# 06-SIM800C.net
KiCad netlist of a schematic drawn in Altium Designer
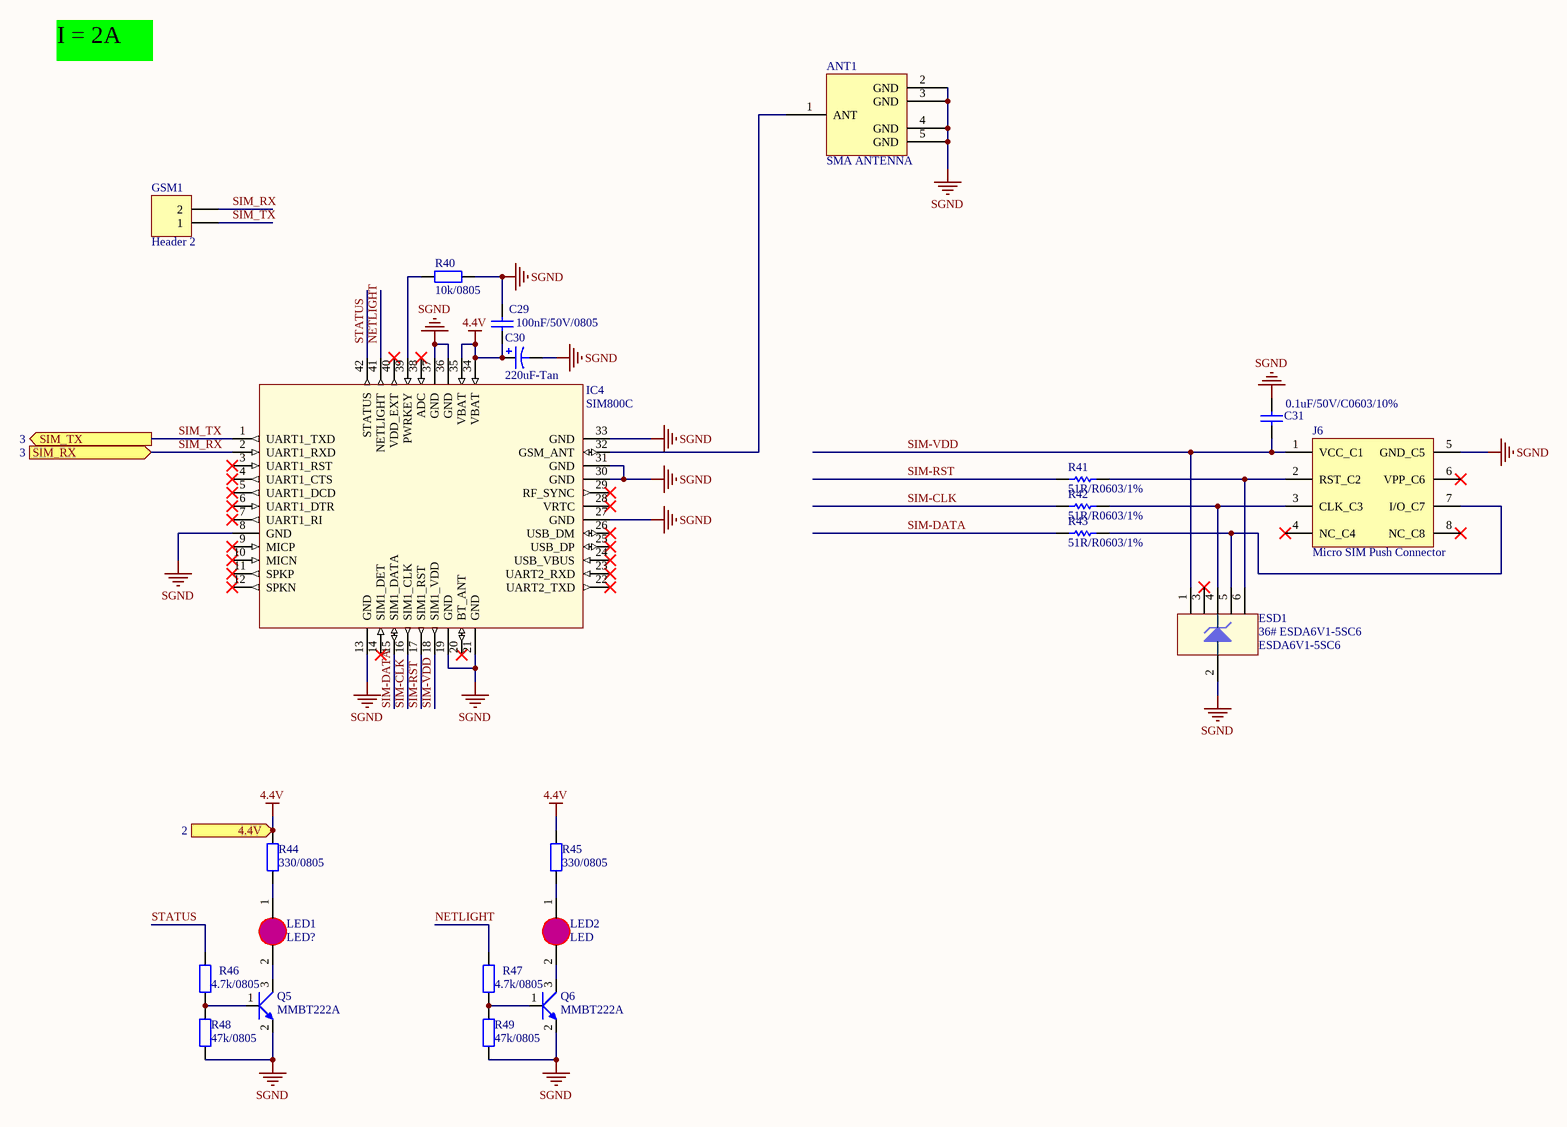
[diagram p0: 06-SIM800C.SchDoc]

(export (version "E")
  (design (tool "Eeschema 10.0.6"))
  (components
    (comp (ref "ANT1")
      (value "SMA ANTENNA")
      (footprint "ANT-SMA-ST-F")
      (libsource (lib "Air_System_lib") (part "SMA ANTENNA"))
    )
    (comp (ref "C29")
      (value "100nF/50V/0805")
      (footprint "Cap Ceramic 0805 SMD")
      (fields (field (name "PUBLISHER") "Altium Limited"))
      (libsource (lib "NBBLib 14-03-2012") (part "CapSMD"))
    )
    (comp (ref "C30")
      (value "220uF-Tan")
      (footprint "CAP TANT CASE E SMD")
      (libsource (lib "Air_System_lib") (part "CAP1210-Tan"))
    )
    (comp (ref "C31")
      (value "0.1uF/50V/C0603/10%")
      (footprint "Cap Ceramic 0603 SMD")
      (description "CAP CER 0.1UF 50V 10% X7R 0603")
      (fields
        (field (name "MANUFACTURER") "Murata Electronics North America")
        (field (name "MANUFACTURER PART NUMBER") "GRM188R71H104KA93D")
      )
      (libsource (lib "GSHT_181013") (part "0.1uF/50V/C0603/10%"))
    )
    (comp (ref "ESD1")
      (value "36# ESDA6V1-5SC6")
      (footprint "36# ESDA6V1-5SC6")
      (description "TRANSIL™ ARRAY FOR ESD PROTECTION")
      (fields (field (name "SUPPLIER PART NUMBER 1") "ESDA6V1-5SC6"))
      (libsource (lib "GSHT_181013") (part "36# ESDA6V1-5SC6"))
    )
    (comp (ref "GSM1")
      (value "Header 2")
      (footprint "Header_2")
      (description "Header, 2-Pin")
      (fields (field (name "PUBLISHER") "Altium Limited"))
      (libsource (lib "NBBLib 14-03-2012") (part "Header 2"))
    )
    (comp (ref "IC4")
      (value "SIM800C")
      (footprint "SIM800C")
      (description "SIM800C V1.00")
      (libsource (lib "LIEMTHANH_LIB") (part "SIM800C"))
    )
    (comp (ref "J6")
      (value "Micro SIM Push Connector")
      (footprint "9# SIM holder")
      (libsource (lib "GSHT_181013") (part "9#SIM Card Holder KF-016"))
    )
    (comp (ref "LED1")
      (value "LED?")
      (footprint "Led 0805R")
      (description "LED SMD 0805")
      (libsource (lib "NBBLib 14-03-2012") (part "LED0805"))
    )
    (comp (ref "LED2")
      (value "LED")
      (footprint "Led 0805R")
      (description "LED SMD 0805")
      (libsource (lib "NBBLib 14-03-2012") (part "LED0805"))
    )
    (comp (ref "Q5")
      (value "MMBT222A")
      (footprint "MMBT2222A")
      (libsource (lib "Air_System_lib") (part "MMBT222A"))
    )
    (comp (ref "Q6")
      (value "MMBT222A")
      (footprint "MMBT2222A")
      (libsource (lib "Air_System_lib") (part "MMBT222A"))
    )
    (comp (ref "R40")
      (value "10k/0805")
      (footprint "RESC2012(0805)")
      (description "Resistor SMD 0805")
      (fields (field (name "PUBLISHER") "Altium Limited"))
      (libsource (lib "") (part "R0805_1"))
    )
    (comp (ref "R41")
      (value "51R/R0603/1%")
      (footprint "Res 0603 SMD")
      (description "RES SMD 22 OHM 1% 1/10W 0603")
      (fields
        (field (name "MANUFACTURER") "Yageo")
        (field (name "MANUFACTURER PART NUMBER") "RC0603FR-0722RL")
      )
      (libsource (lib "GSHT_181013") (part "22R/R0603/1%"))
    )
    (comp (ref "R42")
      (value "51R/R0603/1%")
      (footprint "Res 0603 SMD")
      (description "RES SMD 22 OHM 1% 1/10W 0603")
      (fields
        (field (name "MANUFACTURER") "Yageo")
        (field (name "MANUFACTURER PART NUMBER") "RC0603FR-0722RL")
      )
      (libsource (lib "GSHT_181013") (part "22R/R0603/1%"))
    )
    (comp (ref "R43")
      (value "51R/R0603/1%")
      (footprint "Res 0603 SMD")
      (description "RES SMD 22 OHM 1% 1/10W 0603")
      (fields
        (field (name "MANUFACTURER") "Yageo")
        (field (name "MANUFACTURER PART NUMBER") "RC0603FR-0722RL")
      )
      (libsource (lib "GSHT_181013") (part "22R/R0603/1%"))
    )
    (comp (ref "R44")
      (value "330/0805")
      (footprint "RESC2012(0805)")
      (description "Resistor SMD 0805")
      (fields (field (name "Comment") "R0805") (field (name "PUBLISHER") "Altium Limited"))
      (libsource (lib "NBBLib 14-03-2012") (part "R0805"))
    )
    (comp (ref "R45")
      (value "330/0805")
      (footprint "RESC2012(0805)")
      (description "Resistor SMD 0805")
      (fields (field (name "Comment") "R0805") (field (name "PUBLISHER") "Altium Limited"))
      (libsource (lib "NBBLib 14-03-2012") (part "R0805"))
    )
    (comp (ref "R46")
      (value "4.7k/0805")
      (footprint "RESC2012(0805)")
      (description "Resistor SMD 0805")
      (fields (field (name "Comment") "R0805") (field (name "PUBLISHER") "Altium Limited"))
      (libsource (lib "NBBLib 14-03-2012") (part "R0805"))
    )
    (comp (ref "R47")
      (value "4.7k/0805")
      (footprint "RESC2012(0805)")
      (description "Resistor SMD 0805")
      (fields (field (name "Comment") "R0805") (field (name "PUBLISHER") "Altium Limited"))
      (libsource (lib "NBBLib 14-03-2012") (part "R0805"))
    )
    (comp (ref "R48")
      (value "47k/0805")
      (footprint "RESC2012(0805)")
      (description "Resistor SMD 0805")
      (fields (field (name "Comment") "R0805") (field (name "PUBLISHER") "Altium Limited"))
      (libsource (lib "NBBLib 14-03-2012") (part "R0805"))
    )
    (comp (ref "R49")
      (value "47k/0805")
      (footprint "RESC2012(0805)")
      (description "Resistor SMD 0805")
      (fields (field (name "Comment") "R0805") (field (name "PUBLISHER") "Altium Limited"))
      (libsource (lib "NBBLib 14-03-2012") (part "R0805"))
    )
  )
  (nets
    (net (code "2") (name "/NETLIGHT") (class "Default")
      (node (ref "IC4") (pin "41") (pinfunction "NETLIGHT_41") (pintype "output"))
      (node (ref "R47") (pin "1") (pinfunction "1_1") (pintype "passive"))
    )
    (net (code "3") (name "/SIM-CLK") (class "Default")
      (node (ref "IC4") (pin "16") (pinfunction "SIM1_CLK_16") (pintype "output"))
      (node (ref "R42") (pin "1") (pinfunction "1_1") (pintype "passive"))
    )
    (net (code "4") (name "/SIM-DATA") (class "Default")
      (node (ref "IC4") (pin "15") (pinfunction "SIM1_DATA_15") (pintype "bidirectional"))
      (node (ref "R43") (pin "1") (pinfunction "1_1") (pintype "passive"))
    )
    (net (code "5") (name "/SIM-RST") (class "Default")
      (node (ref "IC4") (pin "17") (pinfunction "SIM1_RST_17") (pintype "output"))
      (node (ref "R41") (pin "1") (pinfunction "1_1") (pintype "passive"))
    )
    (net (code "6") (name "/SIM-VDD") (class "Default")
      (node (ref "C31") (pin "1") (pinfunction "1_1") (pintype "passive"))
      (node (ref "ESD1") (pin "1") (pinfunction "IO1_1") (pintype "passive"))
      (node (ref "IC4") (pin "18") (pinfunction "SIM1_VDD_18") (pintype "output"))
      (node (ref "J6") (pin "1") (pinfunction "VCC_C1_1") (pintype "passive"))
    )
    (net (code "7") (name "/SIM_RX") (class "Default")
      (node (ref "GSM1") (pin "2") (pinfunction "2_2") (pintype "passive"))
      (node (ref "IC4") (pin "2") (pinfunction "UART1_RXD_2") (pintype "input"))
    )
    (net (code "8") (name "/SIM_TX") (class "Default")
      (node (ref "GSM1") (pin "1") (pinfunction "1_1") (pintype "passive"))
      (node (ref "IC4") (pin "1") (pinfunction "UART1_TXD_1") (pintype "output"))
    )
    (net (code "9") (name "/STATUS") (class "Default")
      (node (ref "IC4") (pin "42") (pinfunction "STATUS_42") (pintype "output"))
      (node (ref "R46") (pin "1") (pinfunction "1_1") (pintype "passive"))
    )
    (net (code "10") (name "4.4V") (class "Default")
      (node (ref "C29") (pin "1") (pinfunction "1_1") (pintype "passive"))
      (node (ref "C30") (pin "1") (pinfunction "1_1") (pintype "passive"))
      (node (ref "IC4") (pin "34") (pinfunction "VBAT_34") (pintype "input"))
      (node (ref "IC4") (pin "35") (pinfunction "VBAT_35") (pintype "input"))
      (node (ref "R44") (pin "1") (pinfunction "1_1") (pintype "passive"))
      (node (ref "R45") (pin "1") (pinfunction "1_1") (pintype "passive"))
    )
    (net (code "11") (name "Net-(ANT1-ANT)") (class "Default")
      (node (ref "ANT1") (pin "1") (pinfunction "ANT_1") (pintype "passive"))
      (node (ref "IC4") (pin "32") (pinfunction "GSM_ANT_32") (pintype "bidirectional"))
    )
    (net (code "12") (name "Net-(ESD1-IO3)") (class "Default")
      (node (ref "ESD1") (pin "4") (pinfunction "IO3_4") (pintype "passive"))
      (node (ref "J6") (pin "3") (pinfunction "CLK_C3_3") (pintype "passive"))
      (node (ref "R42") (pin "2") (pinfunction "2_2") (pintype "passive"))
    )
    (net (code "13") (name "Net-(ESD1-IO4)") (class "Default")
      (node (ref "ESD1") (pin "5") (pinfunction "IO4_5") (pintype "passive"))
      (node (ref "J6") (pin "7") (pinfunction "I/O_C7_7") (pintype "passive"))
      (node (ref "R43") (pin "2") (pinfunction "2_2") (pintype "passive"))
    )
    (net (code "14") (name "Net-(ESD1-IO5)") (class "Default")
      (node (ref "ESD1") (pin "6") (pinfunction "IO5_6") (pintype "passive"))
      (node (ref "J6") (pin "2") (pinfunction "RST_C2_2") (pintype "passive"))
      (node (ref "R41") (pin "2") (pinfunction "2_2") (pintype "passive"))
    )
    (net (code "15") (name "Net-(IC4-PWRKEY)") (class "Default")
      (node (ref "IC4") (pin "39") (pinfunction "PWRKEY_39") (pintype "input"))
      (node (ref "R40") (pin "1") (pinfunction "1_1") (pintype "passive"))
    )
    (net (code "16") (name "Net-(LED1-A)") (class "Default")
      (node (ref "LED1") (pin "1") (pinfunction "A_1") (pintype "passive"))
      (node (ref "R44") (pin "2") (pinfunction "2_2") (pintype "passive"))
    )
    (net (code "17") (name "Net-(LED1-K)") (class "Default")
      (node (ref "LED1") (pin "2") (pinfunction "K_2") (pintype "passive"))
      (node (ref "Q5") (pin "3") (pinfunction "3_3") (pintype "passive"))
    )
    (net (code "18") (name "Net-(LED2-A)") (class "Default")
      (node (ref "LED2") (pin "1") (pinfunction "A_1") (pintype "passive"))
      (node (ref "R45") (pin "2") (pinfunction "2_2") (pintype "passive"))
    )
    (net (code "19") (name "Net-(LED2-K)") (class "Default")
      (node (ref "LED2") (pin "2") (pinfunction "K_2") (pintype "passive"))
      (node (ref "Q6") (pin "3") (pinfunction "3_3") (pintype "passive"))
    )
    (net (code "20") (name "Net-(Q5-Pad1)") (class "Default")
      (node (ref "Q5") (pin "1") (pinfunction "1_1") (pintype "passive"))
      (node (ref "R46") (pin "2") (pinfunction "2_2") (pintype "passive"))
      (node (ref "R48") (pin "1") (pinfunction "1_1") (pintype "passive"))
    )
    (net (code "21") (name "Net-(Q6-Pad1)") (class "Default")
      (node (ref "Q6") (pin "1") (pinfunction "1_1") (pintype "passive"))
      (node (ref "R47") (pin "2") (pinfunction "2_2") (pintype "passive"))
      (node (ref "R49") (pin "1") (pinfunction "1_1") (pintype "passive"))
    )
    (net (code "22") (name "SGND") (class "Default")
      (node (ref "ANT1") (pin "2") (pinfunction "GND_2") (pintype "passive"))
      (node (ref "ANT1") (pin "3") (pinfunction "GND_3") (pintype "passive"))
      (node (ref "ANT1") (pin "4") (pinfunction "GND_4") (pintype "passive"))
      (node (ref "ANT1") (pin "5") (pinfunction "GND_5") (pintype "passive"))
      (node (ref "C29") (pin "2") (pinfunction "2_2") (pintype "passive"))
      (node (ref "C30") (pin "2") (pinfunction "2_2") (pintype "passive"))
      (node (ref "C31") (pin "2") (pinfunction "2_2") (pintype "passive"))
      (node (ref "ESD1") (pin "2") (pinfunction "GND_2") (pintype "passive"))
      (node (ref "IC4") (pin "13") (pinfunction "GND_13") (pintype "power_in"))
      (node (ref "IC4") (pin "19") (pinfunction "GND_19") (pintype "power_in"))
      (node (ref "IC4") (pin "21") (pinfunction "GND_21") (pintype "power_in"))
      (node (ref "IC4") (pin "27") (pinfunction "GND_27") (pintype "power_in"))
      (node (ref "IC4") (pin "30") (pinfunction "GND_30") (pintype "power_in"))
      (node (ref "IC4") (pin "31") (pinfunction "GND_31") (pintype "power_in"))
      (node (ref "IC4") (pin "33") (pinfunction "GND_33") (pintype "power_in"))
      (node (ref "IC4") (pin "36") (pinfunction "GND_36") (pintype "power_in"))
      (node (ref "IC4") (pin "37") (pinfunction "GND_37") (pintype "power_in"))
      (node (ref "IC4") (pin "8") (pinfunction "GND_8") (pintype "power_in"))
      (node (ref "J6") (pin "5") (pinfunction "GND_C5_5") (pintype "passive"))
      (node (ref "Q5") (pin "2") (pinfunction "2_2") (pintype "passive"))
      (node (ref "Q6") (pin "2") (pinfunction "2_2") (pintype "passive"))
      (node (ref "R40") (pin "2") (pinfunction "2_2") (pintype "passive"))
      (node (ref "R48") (pin "2") (pinfunction "2_2") (pintype "passive"))
      (node (ref "R49") (pin "2") (pinfunction "2_2") (pintype "passive"))
    )
    (net (code "23") (name "unconnected-(ESD1-IO2-Pad3)") (class "Default")
      (node (ref "ESD1") (pin "3") (pinfunction "IO2_3") (pintype "passive+no_connect"))
    )
    (net (code "24") (name "unconnected-(IC4-ADC-Pad38)") (class "Default")
      (node (ref "IC4") (pin "38") (pinfunction "ADC_38") (pintype "input+no_connect"))
    )
    (net (code "25") (name "unconnected-(IC4-BT_ANT-Pad20)") (class "Default")
      (node (ref "IC4") (pin "20") (pinfunction "BT_ANT_20") (pintype "bidirectional+no_connect"))
    )
    (net (code "26") (name "unconnected-(IC4-MICN-Pad10)") (class "Default")
      (node (ref "IC4") (pin "10") (pinfunction "MICN_10") (pintype "input+no_connect"))
    )
    (net (code "27") (name "unconnected-(IC4-MICP-Pad9)") (class "Default")
      (node (ref "IC4") (pin "9") (pinfunction "MICP_9") (pintype "input+no_connect"))
    )
    (net (code "28") (name "unconnected-(IC4-RF_SYNC-Pad29)") (class "Default")
      (node (ref "IC4") (pin "29") (pinfunction "RF_SYNC_29") (pintype "output+no_connect"))
    )
    (net (code "29") (name "unconnected-(IC4-SIM1_DET-Pad14)") (class "Default")
      (node (ref "IC4") (pin "14") (pinfunction "SIM1_DET_14") (pintype "input+no_connect"))
    )
    (net (code "30") (name "unconnected-(IC4-SPKN-Pad12)") (class "Default")
      (node (ref "IC4") (pin "12") (pinfunction "SPKN_12") (pintype "output+no_connect"))
    )
    (net (code "31") (name "unconnected-(IC4-SPKP-Pad11)") (class "Default")
      (node (ref "IC4") (pin "11") (pinfunction "SPKP_11") (pintype "output+no_connect"))
    )
    (net (code "32") (name "unconnected-(IC4-UART1_CTS-Pad4)") (class "Default")
      (node (ref "IC4") (pin "4") (pinfunction "UART1_CTS_4") (pintype "output+no_connect"))
    )
    (net (code "33") (name "unconnected-(IC4-UART1_DCD-Pad5)") (class "Default")
      (node (ref "IC4") (pin "5") (pinfunction "UART1_DCD_5") (pintype "output+no_connect"))
    )
    (net (code "34") (name "unconnected-(IC4-UART1_DTR-Pad6)") (class "Default")
      (node (ref "IC4") (pin "6") (pinfunction "UART1_DTR_6") (pintype "input+no_connect"))
    )
    (net (code "35") (name "unconnected-(IC4-UART1_RI-Pad7)") (class "Default")
      (node (ref "IC4") (pin "7") (pinfunction "UART1_RI_7") (pintype "output+no_connect"))
    )
    (net (code "36") (name "unconnected-(IC4-UART1_RST-Pad3)") (class "Default")
      (node (ref "IC4") (pin "3") (pinfunction "UART1_RST_3") (pintype "input+no_connect"))
    )
    (net (code "37") (name "unconnected-(IC4-UART2_RXD-Pad23)") (class "Default")
      (node (ref "IC4") (pin "23") (pinfunction "UART2_RXD_23") (pintype "input+no_connect"))
    )
    (net (code "38") (name "unconnected-(IC4-UART2_TXD-Pad22)") (class "Default")
      (node (ref "IC4") (pin "22") (pinfunction "UART2_TXD_22") (pintype "output+no_connect"))
    )
    (net (code "39") (name "unconnected-(IC4-USB_DM-Pad26)") (class "Default")
      (node (ref "IC4") (pin "26") (pinfunction "USB_DM_26") (pintype "bidirectional+no_connect"))
    )
    (net (code "40") (name "unconnected-(IC4-USB_DP-Pad25)") (class "Default")
      (node (ref "IC4") (pin "25") (pinfunction "USB_DP_25") (pintype "bidirectional+no_connect"))
    )
    (net (code "41") (name "unconnected-(IC4-USB_VBUS-Pad24)") (class "Default")
      (node (ref "IC4") (pin "24") (pinfunction "USB_VBUS_24") (pintype "input+no_connect"))
    )
    (net (code "42") (name "unconnected-(IC4-VDD_EXT-Pad40)") (class "Default")
      (node (ref "IC4") (pin "40") (pinfunction "VDD_EXT_40") (pintype "output+no_connect"))
    )
    (net (code "43") (name "unconnected-(IC4-VRTC-Pad28)") (class "Default")
      (node (ref "IC4") (pin "28") (pinfunction "VRTC_28") (pintype "passive+no_connect"))
    )
    (net (code "44") (name "unconnected-(J6-NC_C4-Pad4)") (class "Default")
      (node (ref "J6") (pin "4") (pinfunction "NC_C4_4") (pintype "passive+no_connect"))
    )
    (net (code "45") (name "unconnected-(J6-NC_C8-Pad8)") (class "Default")
      (node (ref "J6") (pin "8") (pinfunction "NC_C8_8") (pintype "passive+no_connect"))
    )
    (net (code "46") (name "unconnected-(J6-VPP_C6-Pad6)") (class "Default")
      (node (ref "J6") (pin "6") (pinfunction "VPP_C6_6") (pintype "passive+no_connect"))
    )
  )
)
